# 28Pins_Schematic.net
KiCad netlist of a schematic drawn in Altium Designer
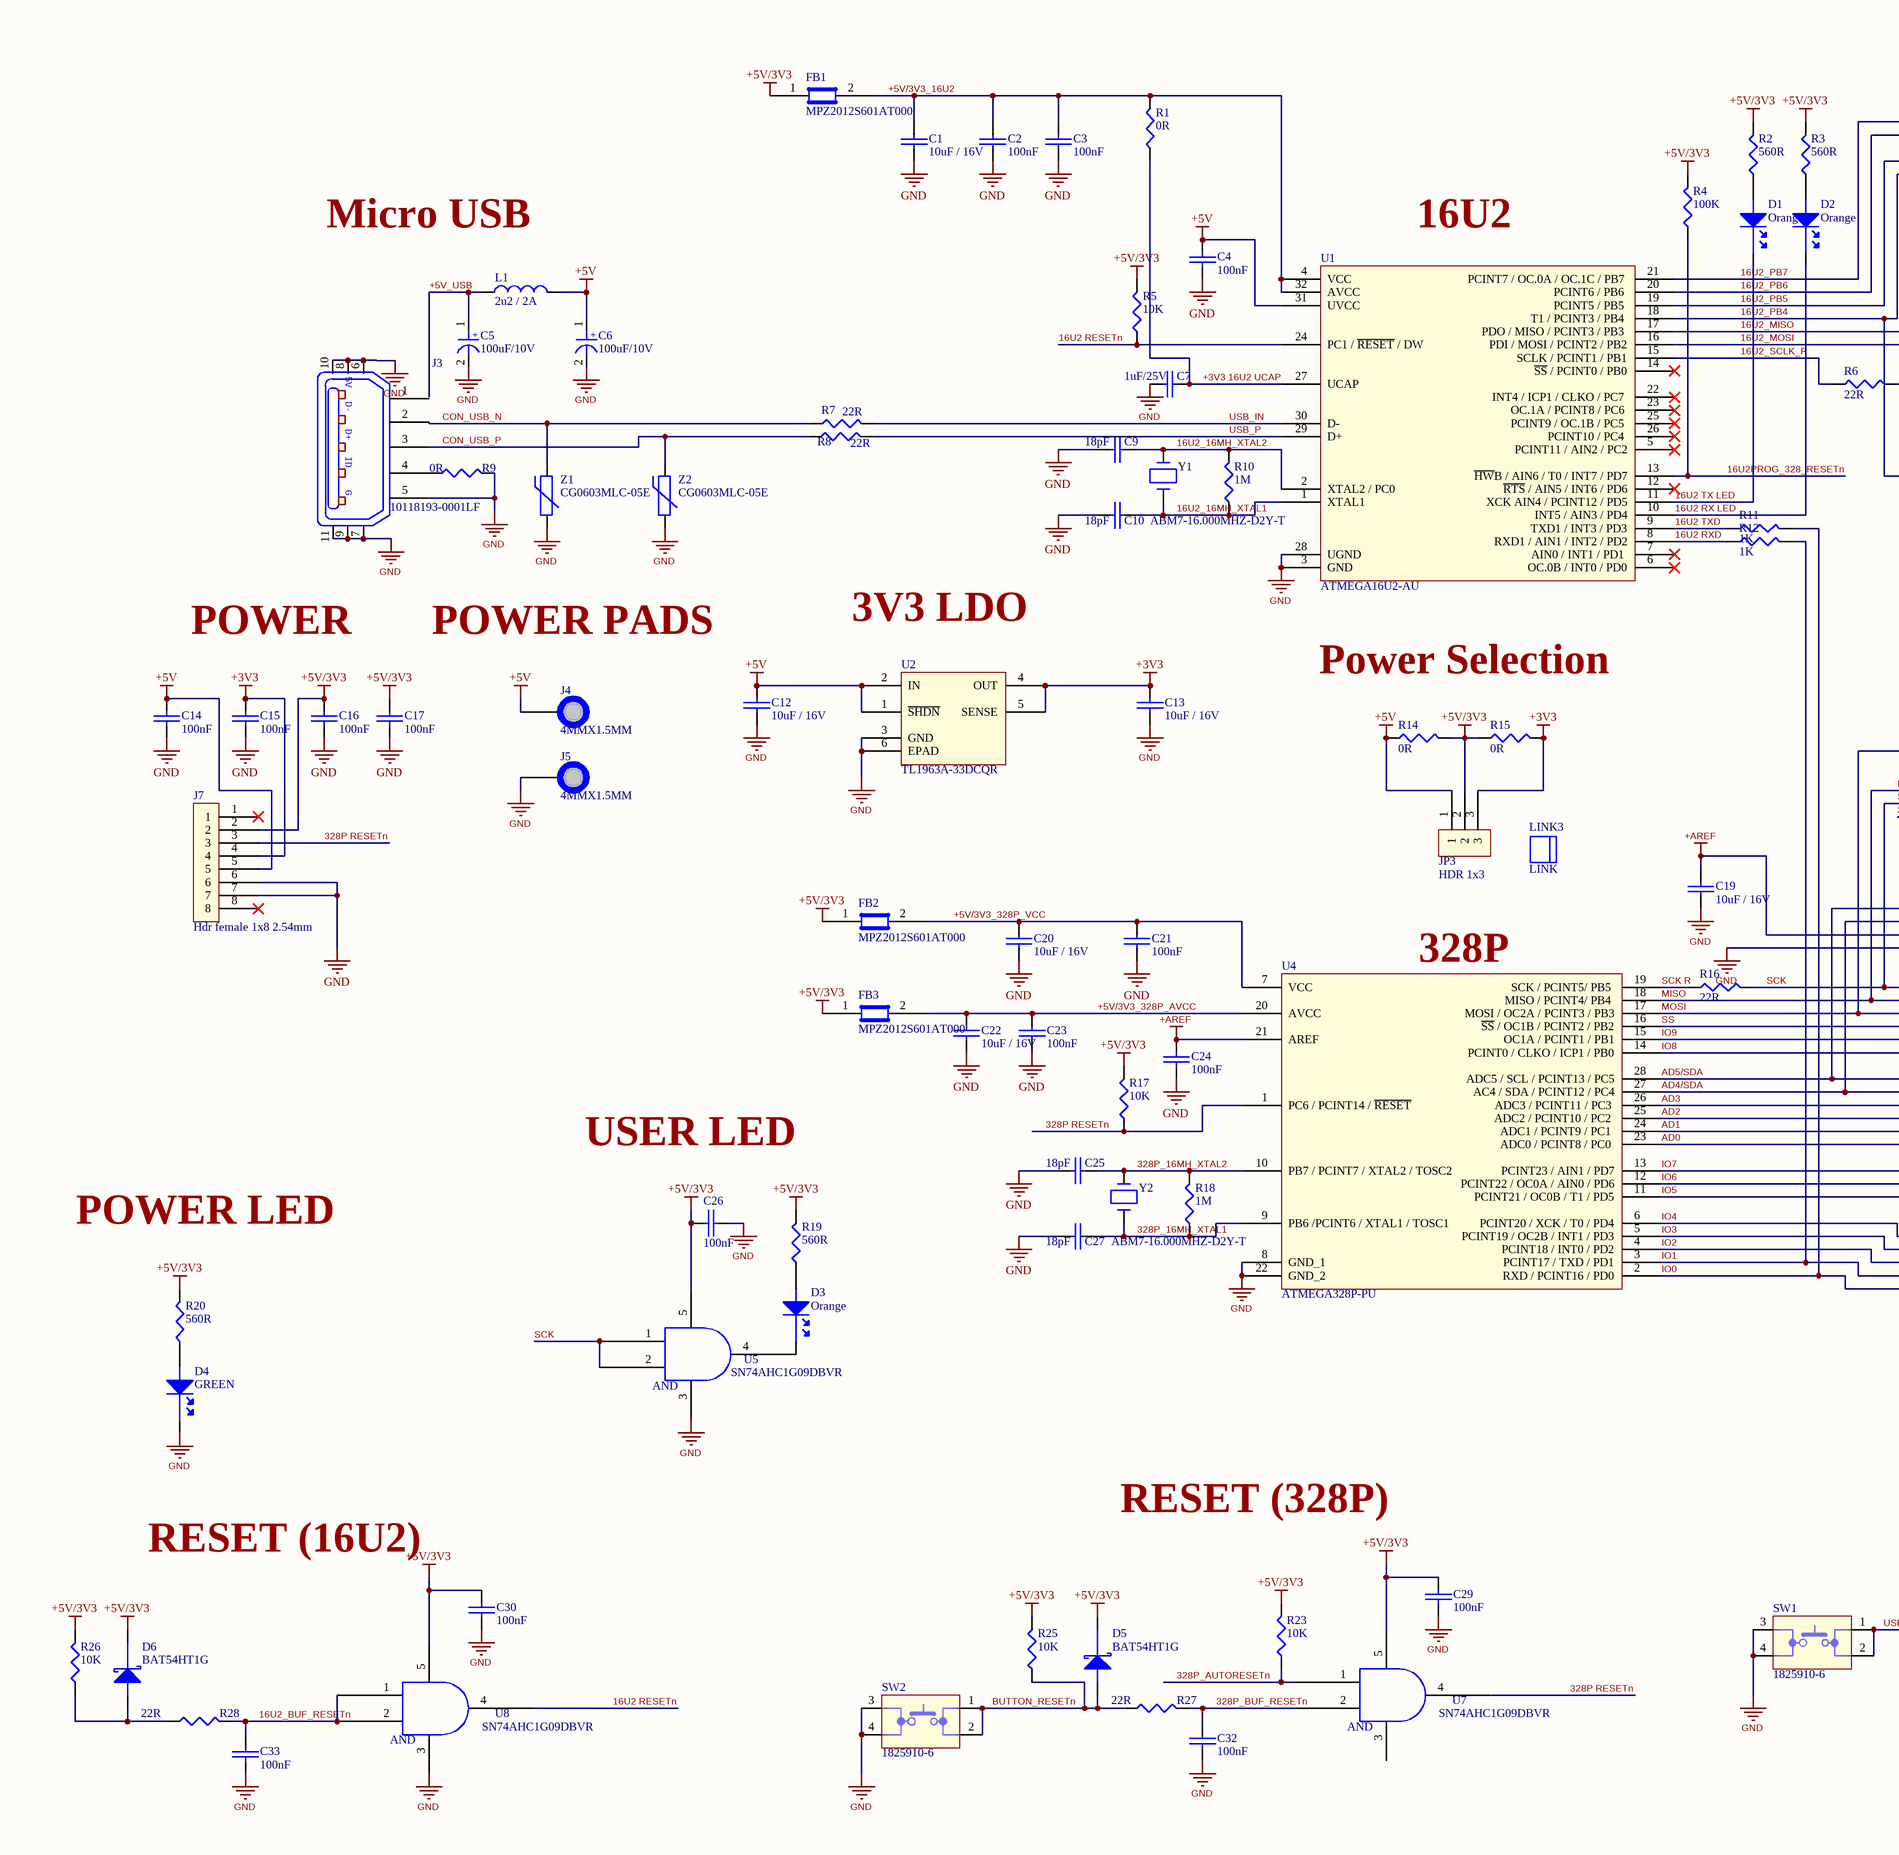
[diagram p0: 28Pins_Schematic.SchDoc, left]
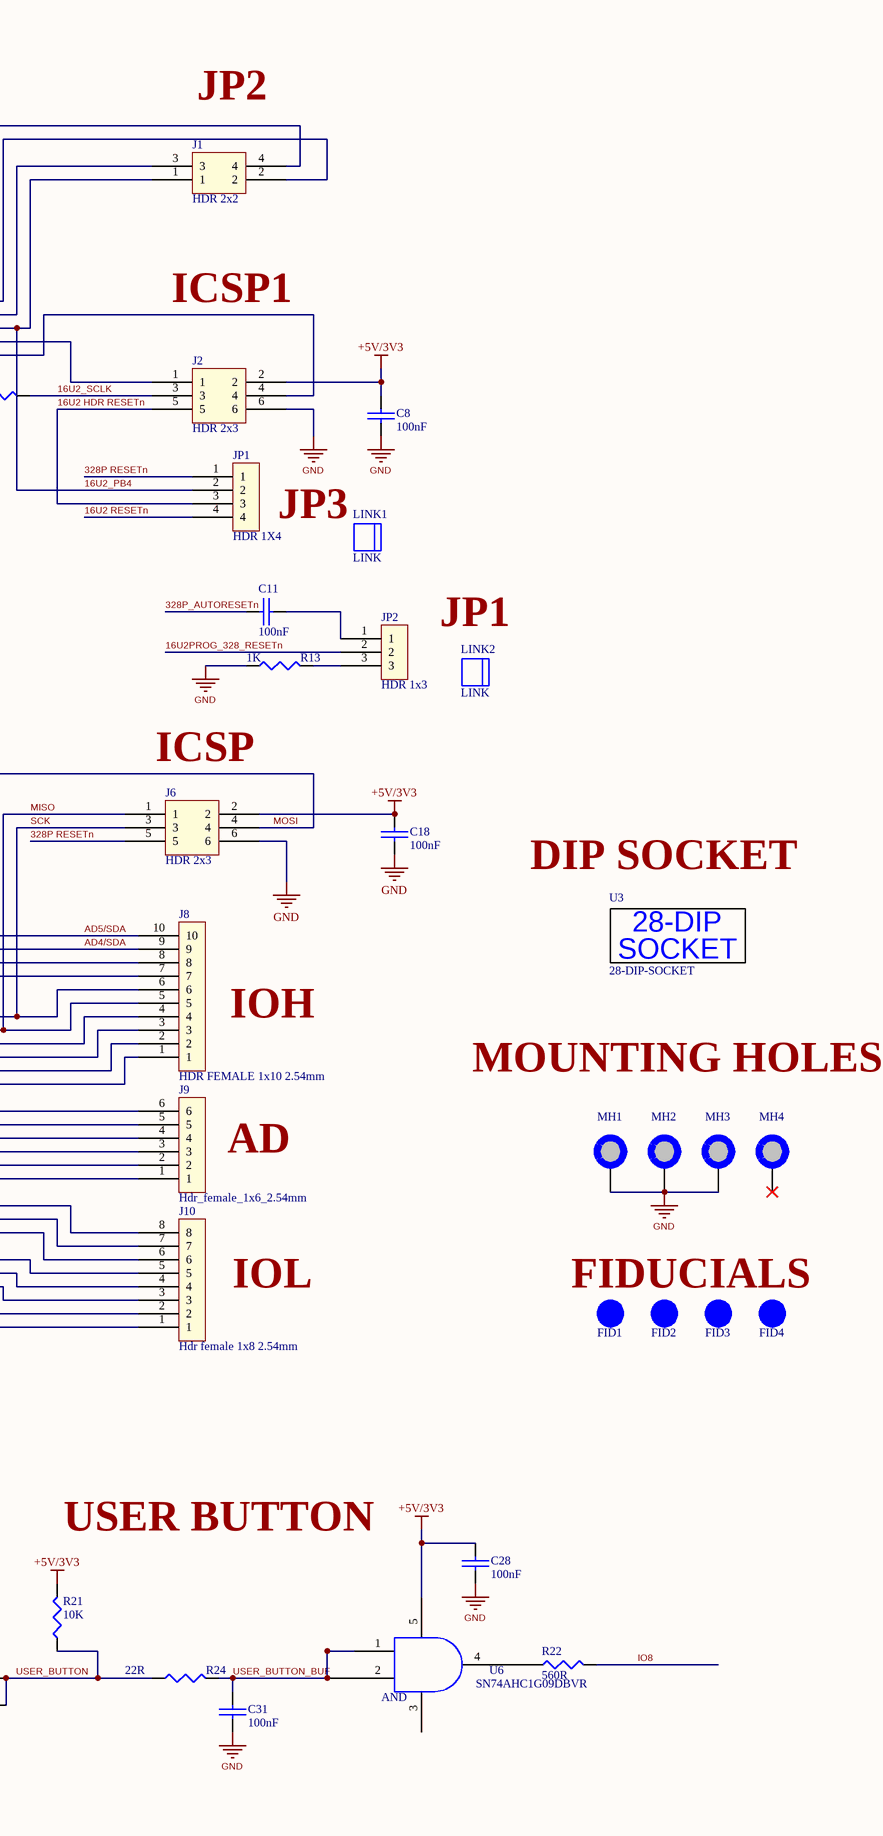
[diagram p1: 28Pins_Schematic.SchDoc, right]

(export (version "E")
  (design (tool "Eeschema 10.0.6"))
  (components
    (comp (ref "C1")
      (value "10uF / 16V")
      (footprint "C0805")
      (fields (field (name "TOLERANCE") "20%"))
      (libsource (lib "28Pins_Project_Schlib") (part "C2012X5R1C106M125AC"))
    )
    (comp (ref "C2")
      (value "100nF")
      (footprint "C0805")
      (fields (field (name "TOLERANCE") "10%") (field (name "VOLTAGE") "50V"))
      (libsource (lib "28Pins_Project_Schlib") (part "C2012X7R1H104K085AA"))
    )
    (comp (ref "C3")
      (value "100nF")
      (footprint "C0805")
      (fields (field (name "TOLERANCE") "10%") (field (name "VOLTAGE") "50V"))
      (libsource (lib "28Pins_Project_Schlib") (part "C2012X7R1H104K085AA"))
    )
    (comp (ref "C4")
      (value "100nF")
      (footprint "C0805")
      (fields (field (name "TOLERANCE") "10%") (field (name "VOLTAGE") "50V"))
      (libsource (lib "28Pins_Project_Schlib") (part "C2012X7R1H104K085AA"))
    )
    (comp (ref "C5")
      (value "100uF/10V")
      (footprint "C_ALU_C_SIZE")
      (description "Cap Aluminum 100uF 10V 20% (5 X 5.4mm) SMD 50mA 1000 hr 85°C T/R")
      (fields (field (name "TOLERANCE") "20%"))
      (libsource (lib "28Pins_Project_Schlib") (part "EEE-1AA101WR"))
    )
    (comp (ref "C6")
      (value "100uF/10V")
      (footprint "C_ALU_C_SIZE")
      (description "Cap Aluminum 100uF 10V 20% (5 X 5.4mm) SMD 50mA 1000 hr 85°C T/R")
      (fields (field (name "TOLERANCE") "20%"))
      (libsource (lib "28Pins_Project_Schlib") (part "EEE-1AA101WR"))
    )
    (comp (ref "C7")
      (value "1uF/25V")
      (footprint "C0805")
      (fields (field (name "TOLERANCE") "10%") (field (name "VOLTAGE") "25V"))
      (libsource (lib "28Pins_Project_Schlib") (part "C2012X5R1E105K125AA"))
    )
    (comp (ref "C8")
      (value "100nF")
      (footprint "C0805")
      (fields (field (name "TOLERANCE") "10%") (field (name "VOLTAGE") "50V"))
      (libsource (lib "28Pins_Project_Schlib") (part "C2012X7R1H104K085AA"))
    )
    (comp (ref "C9")
      (value "18pF")
      (footprint "C0805")
      (description "CAP CER 18PF 50V C0G/NP0 0805")
      (fields (field (name "VOLTAGE") "50V") (field (name "TOLERANCE") "5%"))
      (libsource (lib "28Pins_Project_Schlib") (part "C0805C180J5GACTU"))
    )
    (comp (ref "C10")
      (value "18pF")
      (footprint "C0805")
      (description "CAP CER 18PF 50V C0G/NP0 0805")
      (fields (field (name "VOLTAGE") "50V") (field (name "TOLERANCE") "5%"))
      (libsource (lib "28Pins_Project_Schlib") (part "C0805C180J5GACTU"))
    )
    (comp (ref "C11")
      (value "100nF")
      (footprint "C0805")
      (fields (field (name "TOLERANCE") "10%") (field (name "VOLTAGE") "50V"))
      (libsource (lib "28Pins_Project_Schlib") (part "C2012X7R1H104K085AA"))
    )
    (comp (ref "C12")
      (value "10uF / 16V")
      (footprint "C0805")
      (fields (field (name "TOLERANCE") "20%"))
      (libsource (lib "28Pins_Project_Schlib") (part "C2012X5R1C106M125AC"))
    )
    (comp (ref "C13")
      (value "10uF / 16V")
      (footprint "C0805")
      (fields (field (name "TOLERANCE") "20%"))
      (libsource (lib "28Pins_Project_Schlib") (part "C2012X5R1C106M125AC"))
    )
    (comp (ref "C14")
      (value "100nF")
      (footprint "C0805")
      (fields (field (name "TOLERANCE") "10%") (field (name "VOLTAGE") "50V"))
      (libsource (lib "28Pins_Project_Schlib") (part "C2012X7R1H104K085AA"))
    )
    (comp (ref "C15")
      (value "100nF")
      (footprint "C0805")
      (fields (field (name "TOLERANCE") "10%") (field (name "VOLTAGE") "50V"))
      (libsource (lib "28Pins_Project_Schlib") (part "C2012X7R1H104K085AA"))
    )
    (comp (ref "C16")
      (value "100nF")
      (footprint "C0805")
      (fields (field (name "TOLERANCE") "10%") (field (name "VOLTAGE") "50V"))
      (libsource (lib "28Pins_Project_Schlib") (part "C2012X7R1H104K085AA"))
    )
    (comp (ref "C17")
      (value "100nF")
      (footprint "C0805")
      (fields (field (name "TOLERANCE") "10%") (field (name "VOLTAGE") "50V"))
      (libsource (lib "28Pins_Project_Schlib") (part "C2012X7R1H104K085AA"))
    )
    (comp (ref "C18")
      (value "100nF")
      (footprint "C0805")
      (fields (field (name "TOLERANCE") "10%") (field (name "VOLTAGE") "50V"))
      (libsource (lib "28Pins_Project_Schlib") (part "C2012X7R1H104K085AA"))
    )
    (comp (ref "C19")
      (value "10uF / 16V")
      (footprint "C0805")
      (fields (field (name "TOLERANCE") "20%"))
      (libsource (lib "28Pins_Project_Schlib") (part "C2012X5R1C106M125AC"))
    )
    (comp (ref "C20")
      (value "10uF / 16V")
      (footprint "C0805")
      (fields (field (name "TOLERANCE") "20%"))
      (libsource (lib "28Pins_Project_Schlib") (part "C2012X5R1C106M125AC"))
    )
    (comp (ref "C21")
      (value "100nF")
      (footprint "C0805")
      (fields (field (name "TOLERANCE") "10%") (field (name "VOLTAGE") "50V"))
      (libsource (lib "28Pins_Project_Schlib") (part "C2012X7R1H104K085AA"))
    )
    (comp (ref "C22")
      (value "10uF / 16V")
      (footprint "C0805")
      (fields (field (name "TOLERANCE") "20%"))
      (libsource (lib "28Pins_Project_Schlib") (part "C2012X5R1C106M125AC"))
    )
    (comp (ref "C23")
      (value "100nF")
      (footprint "C0805")
      (fields (field (name "TOLERANCE") "10%") (field (name "VOLTAGE") "50V"))
      (libsource (lib "28Pins_Project_Schlib") (part "C2012X7R1H104K085AA"))
    )
    (comp (ref "C24")
      (value "100nF")
      (footprint "C0805")
      (fields (field (name "TOLERANCE") "10%") (field (name "VOLTAGE") "50V"))
      (libsource (lib "28Pins_Project_Schlib") (part "C2012X7R1H104K085AA"))
    )
    (comp (ref "C25")
      (value "18pF")
      (footprint "C0805")
      (description "CAP CER 18PF 50V C0G/NP0 0805")
      (fields (field (name "VOLTAGE") "50V") (field (name "TOLERANCE") "5%"))
      (libsource (lib "28Pins_Project_Schlib") (part "C0805C180J5GACTU"))
    )
    (comp (ref "C26")
      (value "100nF")
      (footprint "C0805")
      (fields (field (name "TOLERANCE") "10%") (field (name "VOLTAGE") "50V"))
      (libsource (lib "28Pins_Project_Schlib") (part "C2012X7R1H104K085AA"))
    )
    (comp (ref "C27")
      (value "18pF")
      (footprint "C0805")
      (description "CAP CER 18PF 50V C0G/NP0 0805")
      (fields (field (name "VOLTAGE") "50V") (field (name "TOLERANCE") "5%"))
      (libsource (lib "28Pins_Project_Schlib") (part "C0805C180J5GACTU"))
    )
    (comp (ref "C28")
      (value "100nF")
      (footprint "C0805")
      (fields (field (name "TOLERANCE") "10%") (field (name "VOLTAGE") "50V"))
      (libsource (lib "28Pins_Project_Schlib") (part "C2012X7R1H104K085AA"))
    )
    (comp (ref "C29")
      (value "100nF")
      (footprint "C0805")
      (fields (field (name "TOLERANCE") "10%") (field (name "VOLTAGE") "50V"))
      (libsource (lib "28Pins_Project_Schlib") (part "C2012X7R1H104K085AA"))
    )
    (comp (ref "C30")
      (value "100nF")
      (footprint "C0805")
      (fields (field (name "TOLERANCE") "10%") (field (name "VOLTAGE") "50V"))
      (libsource (lib "28Pins_Project_Schlib") (part "C2012X7R1H104K085AA"))
    )
    (comp (ref "C31")
      (value "100nF")
      (footprint "C0805")
      (fields (field (name "TOLERANCE") "10%") (field (name "VOLTAGE") "50V"))
      (libsource (lib "28Pins_Project_Schlib") (part "C2012X7R1H104K085AA"))
    )
    (comp (ref "C32")
      (value "100nF")
      (footprint "C0805")
      (fields (field (name "TOLERANCE") "10%") (field (name "VOLTAGE") "50V"))
      (libsource (lib "28Pins_Project_Schlib") (part "C2012X7R1H104K085AA"))
    )
    (comp (ref "C33")
      (value "100nF")
      (footprint "C0805")
      (fields (field (name "TOLERANCE") "10%") (field (name "VOLTAGE") "50V"))
      (libsource (lib "28Pins_Project_Schlib") (part "C2012X7R1H104K085AA"))
    )
    (comp (ref "D1")
      (value "Orange")
      (footprint "LED_0603")
      (description "OSRAM - LO L29K-H2K1-24-Z - SMARTLED 0603 ORANGE")
      (libsource (lib "28Pins_Project_Schlib") (part "LOL29K-H2K1-24-Z"))
    )
    (comp (ref "D2")
      (value "Orange")
      (footprint "LED_0603")
      (description "OSRAM - LO L29K-H2K1-24-Z - SMARTLED 0603 ORANGE")
      (libsource (lib "28Pins_Project_Schlib") (part "LOL29K-H2K1-24-Z"))
    )
    (comp (ref "D3")
      (value "Orange")
      (footprint "LED_0603")
      (description "OSRAM - LO L29K-H2K1-24-Z - SMARTLED 0603 ORANGE")
      (libsource (lib "28Pins_Project_Schlib") (part "LOL29K-H2K1-24-Z"))
    )
    (comp (ref "D4")
      (value "GREEN")
      (footprint "LED_0603")
      (description "LED Uni-Color Green 572nm 2-Pin Chip 0603(1608Metric) T/R")
      (libsource (lib "28Pins_Project_Schlib") (part "LGL29K-G2J1-24-Z"))
    )
    (comp (ref "D5")
      (value "BAT54HT1G")
      (footprint "SOD323")
      (description "Small Signal Schottky Diode, Single, 30 V, 200 mA, 800 mV, 600 mA, 150 C ;RoHS Compliant: Yes")
      (libsource (lib "28Pins_Project_Schlib") (part "BAT54HT1G"))
    )
    (comp (ref "D6")
      (value "BAT54HT1G")
      (footprint "SOD323")
      (description "Small Signal Schottky Diode, Single, 30 V, 200 mA, 800 mV, 600 mA, 150 C ;RoHS Compliant: Yes")
      (libsource (lib "28Pins_Project_Schlib") (part "BAT54HT1G"))
    )
    (comp (ref "FB1")
      (value "MPZ2012S601AT000")
      (footprint "C0805")
      (description "FERRITE BEAD 600 OHM 0805 1LN")
      (libsource (lib "28Pins_Project_Schlib") (part "MPZ2012S601AT000"))
    )
    (comp (ref "FB2")
      (value "MPZ2012S601AT000")
      (footprint "C0805")
      (description "FERRITE BEAD 600 OHM 0805 1LN")
      (libsource (lib "28Pins_Project_Schlib") (part "MPZ2012S601AT000"))
    )
    (comp (ref "FB3")
      (value "MPZ2012S601AT000")
      (footprint "C0805")
      (description "FERRITE BEAD 600 OHM 0805 1LN")
      (libsource (lib "28Pins_Project_Schlib") (part "MPZ2012S601AT000"))
    )
    (comp (ref "FID1")
      (value "FID_1MMC")
      (footprint "FID_40X120D")
      (description "Fiducial 40mill Diameter,120mil Mask")
      (libsource (lib "28Pins_Project_Schlib") (part "FID_1MM"))
    )
    (comp (ref "FID2")
      (value "FID_1MMC")
      (footprint "FID_40X120D")
      (description "Fiducial 40mill Diameter,120mil Mask")
      (libsource (lib "28Pins_Project_Schlib") (part "FID_1MM"))
    )
    (comp (ref "FID3")
      (value "FID_1MMC")
      (footprint "FID_40X120D")
      (description "Fiducial 40mill Diameter,120mil Mask")
      (libsource (lib "28Pins_Project_Schlib") (part "FID_1MM"))
    )
    (comp (ref "FID4")
      (value "FID_1MMC")
      (footprint "FID_40X120D")
      (description "Fiducial 40mill Diameter,120mil Mask")
      (libsource (lib "28Pins_Project_Schlib") (part "FID_1MM"))
    )
    (comp (ref "J1")
      (value "HDR 2x2")
      (footprint "HDR _2x2_2.54mm")
      (description "CONN HEADER VERT 4POS 2.54MM")
      (libsource (lib "28Pins_Project_Schlib") (part "68602-204HLF"))
    )
    (comp (ref "J2")
      (value "HDR 2x3")
      (footprint "HDR _2x3_2.54mm - duplicate")
      (description "CONN HEADER 6POS .100 STR 30AU")
      (libsource (lib "28Pins_Project_Schlib") (part "67997-106HLF"))
    )
    (comp (ref "J3")
      (value "10118193-0001LF")
      (footprint "10118193")
      (description "CONN USB MICRO B RECPT SMT R/A")
      (libsource (lib "28Pins_Project_Schlib") (part "10118193-0001LF"))
    )
    (comp (ref "J4")
      (value "4MMX1.5MM")
      (footprint "PAD_WITH_HOLE_4MMX1.5MM")
      (description "PAD_WITH_HOLE_4MMX1.5MM")
      (libsource (lib "28Pins_Project_Schlib") (part "PAD_WITH_HOLE_4MMX1.5MM"))
    )
    (comp (ref "J5")
      (value "4MMX1.5MM")
      (footprint "PAD_WITH_HOLE_4MMX1.5MM")
      (description "PAD_WITH_HOLE_4MMX1.5MM")
      (libsource (lib "28Pins_Project_Schlib") (part "PAD_WITH_HOLE_4MMX1.5MM"))
    )
    (comp (ref "J6")
      (value "HDR 2x3")
      (footprint "HDR _2x3_2.54mm - duplicate")
      (description "CONN HEADER 6POS .100 STR 30AU")
      (libsource (lib "28Pins_Project_Schlib") (part "67997-106HLF"))
    )
    (comp (ref "J7")
      (value "Hdr female 1x8 2.54mm")
      (footprint "Hdr_Female_1x8_2.54mm - duplicate")
      (description "2.54mm (0.1\") Pitch SIL Vertical PC Tail Socket Assembly, selective gold + tin, 8 contacts")
      (libsource (lib "28Pins_Project_Schlib") (part "M20-7820842"))
    )
    (comp (ref "J8")
      (value "HDR FEMALE 1x10 2.54mm")
      (footprint "Hdr_Female_1x10_2.54mm - duplicate")
      (description "Headers & Wire Housings 10 PIN SIL VERTICAL SOCKET GOLD+TIN")
      (libsource (lib "28Pins_Project_Schlib") (part "M20-7821042"))
    )
    (comp (ref "J9")
      (value "Hdr_female_1x6_2.54mm")
      (footprint "Hdr_Female_1x6_2.54mm - duplicate - duplicate")
      (description "06-WAY SIL VERT SOCKET L/FREE")
      (libsource (lib "28Pins_Project_Schlib") (part "M20-7820646"))
    )
    (comp (ref "J10")
      (value "Hdr female 1x8 2.54mm")
      (footprint "Hdr_Female_1x8_2.54mm - duplicate")
      (description "2.54mm (0.1\") Pitch SIL Vertical PC Tail Socket Assembly, selective gold + tin, 8 contacts")
      (libsource (lib "") (part "M20-7820842_1"))
    )
    (comp (ref "JP1")
      (value "HDR 1X4")
      (footprint "HDR_1X4_2.54mm")
      (description "CONN HEADER VERT 4POS 2.54MM")
      (libsource (lib "28Pins_Project_Schlib") (part "68001-204HLF"))
    )
    (comp (ref "JP2")
      (value "HDR 1x3")
      (footprint "HDR 1x3 2.54mm")
      (description "Conn Unshrouded Header HDR 3 POS 2.54mm Solder ST Thru-Hole Bulk")
      (libsource (lib "") (part "68000-103HLF_1"))
    )
    (comp (ref "JP3")
      (value "HDR 1x3")
      (footprint "HDR 1x3 2.54mm")
      (description "Conn Unshrouded Header HDR 3 POS 2.54mm Solder ST Thru-Hole Bulk")
      (libsource (lib "28Pins_Project_Schlib") (part "68000-103HLF"))
    )
    (comp (ref "L1")
      (value "2u2 / 2A")
      (footprint "C1210_IND")
      (description "FIXED IND 2.2UH 2A 80 MOHM SMD")
      (fields (field (name "TOLERANCE") "20%"))
      (libsource (lib "28Pins_Project_Schlib") (part "L1210R2R2MDWIT"))
    )
    (comp (ref "LINK1")
      (value "LINK")
      (description "CONN JUMPER SHORTING .100\" GOLD")
      (libsource (lib "28Pins_Project_Schlib") (part "QPC02SXGN-RC"))
    )
    (comp (ref "LINK2")
      (value "LINK")
      (description "CONN JUMPER SHORTING .100\" GOLD")
      (libsource (lib "28Pins_Project_Schlib") (part "QPC02SXGN-RC"))
    )
    (comp (ref "LINK3")
      (value "LINK")
      (description "CONN JUMPER SHORTING .100\" GOLD")
      (libsource (lib "28Pins_Project_Schlib") (part "QPC02SXGN-RC"))
    )
    (comp (ref "MH1")
      (value "MH_7.4MMC_3.2MMD")
      (footprint "MH_7.4MMD_3.2MMD")
      (description "Mounting Hole 7.4mm Diameter, 3.2mm Drill")
      (libsource (lib "28Pins_Project_Schlib") (part "MH_7.4MMC_3.2MMD"))
    )
    (comp (ref "MH2")
      (value "MH_7.4MMC_3.2MMD")
      (footprint "MH_7.4MMD_3.2MMD")
      (description "Mounting Hole 7.4mm Diameter, 3.2mm Drill")
      (libsource (lib "28Pins_Project_Schlib") (part "MH_7.4MMC_3.2MMD"))
    )
    (comp (ref "MH3")
      (value "MH_7.4MMC_3.2MMD")
      (footprint "MH_7.4MMD_3.2MMD")
      (description "Mounting Hole 7.4mm Diameter, 3.2mm Drill")
      (libsource (lib "28Pins_Project_Schlib") (part "MH_7.4MMC_3.2MMD"))
    )
    (comp (ref "MH4")
      (value "MH_7.4MMNC_3.2MMD")
      (footprint "MH_7.4MMD_3.2MMD_NON_COPPER_NPTH")
      (description "Hole 7.4mm Diameter (Non Copper), 3.2mm Drill NPTH")
      (libsource (lib "28Pins_Project_Schlib") (part "MH_7.4MMNC_3.2MMD"))
    )
    (comp (ref "R1")
      (value "0R")
      (footprint "R0805")
      (description "Surface Mount Thick Film Resistor, RC Series, 125 mW, - 5%, 150 V, 0805 [2012 Metric]")
      (fields (field (name "TOLERANCE") "5%"))
      (libsource (lib "28Pins_Project_Schlib") (part "RC0805JR-070RL"))
    )
    (comp (ref "R2")
      (value "560R")
      (footprint "R0805")
      (description "Surface Mount Thick Film Resistor, RC Series, 560 ohm, 125 mW, - 1%, 150 V, 0805 [2012 Metric]")
      (fields (field (name "TOLERANCE") "1%"))
      (libsource (lib "28Pins_Project_Schlib") (part "RC0805FR-07560RL"))
    )
    (comp (ref "R3")
      (value "560R")
      (footprint "R0805")
      (description "Surface Mount Thick Film Resistor, RC Series, 560 ohm, 125 mW, - 1%, 150 V, 0805 [2012 Metric]")
      (fields (field (name "TOLERANCE") "1%"))
      (libsource (lib "28Pins_Project_Schlib") (part "RC0805FR-07560RL"))
    )
    (comp (ref "R4")
      (value "100K")
      (footprint "R0805")
      (description "YAGEO         RC0805FR-07100KL            RES, THICK FILM, 100K, 1%, 0.125W, 0805, REEL")
      (fields (field (name "TOLERANCE") "1%"))
      (libsource (lib "28Pins_Project_Schlib") (part "RC0805FR-07100KL"))
    )
    (comp (ref "R5")
      (value "10K")
      (footprint "R0805")
      (description "RES SMD 10K OHM 1% 1/8W 0805")
      (fields (field (name "TOLERANCE") "1%"))
      (libsource (lib "28Pins_Project_Schlib") (part "RC0805FR-0710KL"))
    )
    (comp (ref "R6")
      (value "22R")
      (footprint "R0805")
      (fields (field (name "TOLERANCE") "1%"))
      (libsource (lib "28Pins_Project_Schlib") (part "RC0805FR-07220RL"))
    )
    (comp (ref "R7")
      (value "22R")
      (footprint "R0805")
      (fields (field (name "TOLERANCE") "1%"))
      (libsource (lib "28Pins_Project_Schlib") (part "RC0805FR-07220RL"))
    )
    (comp (ref "R8")
      (value "22R")
      (footprint "R0805")
      (fields (field (name "TOLERANCE") "1%"))
      (libsource (lib "28Pins_Project_Schlib") (part "RC0805FR-07220RL"))
    )
    (comp (ref "R9")
      (value "0R")
      (footprint "R0805")
      (description "Surface Mount Thick Film Resistor, RC Series, 125 mW, - 5%, 150 V, 0805 [2012 Metric]")
      (fields (field (name "TOLERANCE") "5%"))
      (libsource (lib "28Pins_Project_Schlib") (part "RC0805JR-070RL"))
    )
    (comp (ref "R10")
      (value "1M")
      (footprint "R0805")
      (description "RES SMD 1M OHM 1% 1/8W 0805")
      (fields (field (name "TOLERANCE") "1%"))
      (libsource (lib "28Pins_Project_Schlib") (part "RC0805FR-071ML"))
    )
    (comp (ref "R11")
      (value "1K")
      (footprint "R0805")
      (fields (field (name "TOLERANCE") "1%"))
      (libsource (lib "28Pins_Project_Schlib") (part "RC0805FR-071KL"))
    )
    (comp (ref "R12")
      (value "1K")
      (footprint "R0805")
      (fields (field (name "TOLERANCE") "1%"))
      (libsource (lib "28Pins_Project_Schlib") (part "RC0805FR-071KL"))
    )
    (comp (ref "R13")
      (value "1K")
      (footprint "R0805")
      (fields (field (name "TOLERANCE") "1%"))
      (libsource (lib "28Pins_Project_Schlib") (part "RC0805FR-071KL"))
    )
    (comp (ref "R14")
      (value "0R")
      (footprint "R0805")
      (description "Surface Mount Thick Film Resistor, RC Series, 125 mW, - 5%, 150 V, 0805 [2012 Metric]")
      (fields (field (name "TOLERANCE") "5%"))
      (libsource (lib "28Pins_Project_Schlib") (part "RC0805JR-070RL"))
    )
    (comp (ref "R15")
      (value "0R")
      (footprint "R0805")
      (description "Surface Mount Thick Film Resistor, RC Series, 125 mW, - 5%, 150 V, 0805 [2012 Metric]")
      (fields (field (name "TOLERANCE") "5%"))
      (libsource (lib "28Pins_Project_Schlib") (part "RC0805JR-070RL"))
    )
    (comp (ref "R16")
      (value "22R")
      (footprint "R0805")
      (fields (field (name "TOLERANCE") "1%"))
      (libsource (lib "28Pins_Project_Schlib") (part "RC0805FR-07220RL"))
    )
    (comp (ref "R17")
      (value "10K")
      (footprint "R0805")
      (description "RES SMD 10K OHM 1% 1/8W 0805")
      (fields (field (name "TOLERANCE") "1%"))
      (libsource (lib "28Pins_Project_Schlib") (part "RC0805FR-0710KL"))
    )
    (comp (ref "R18")
      (value "1M")
      (footprint "R0805")
      (description "RES SMD 1M OHM 1% 1/8W 0805")
      (fields (field (name "TOLERANCE") "1%"))
      (libsource (lib "28Pins_Project_Schlib") (part "RC0805FR-071ML"))
    )
    (comp (ref "R19")
      (value "560R")
      (footprint "R0805")
      (description "Surface Mount Thick Film Resistor, RC Series, 560 ohm, 125 mW, - 1%, 150 V, 0805 [2012 Metric]")
      (fields (field (name "TOLERANCE") "1%"))
      (libsource (lib "28Pins_Project_Schlib") (part "RC0805FR-07560RL"))
    )
    (comp (ref "R20")
      (value "560R")
      (footprint "R0805")
      (description "Surface Mount Thick Film Resistor, RC Series, 560 ohm, 125 mW, - 1%, 150 V, 0805 [2012 Metric]")
      (fields (field (name "TOLERANCE") "1%"))
      (libsource (lib "28Pins_Project_Schlib") (part "RC0805FR-07560RL"))
    )
    (comp (ref "R21")
      (value "10K")
      (footprint "R0805")
      (description "RES SMD 10K OHM 1% 1/8W 0805")
      (fields (field (name "TOLERANCE") "1%"))
      (libsource (lib "28Pins_Project_Schlib") (part "RC0805FR-0710KL"))
    )
    (comp (ref "R22")
      (value "560R")
      (footprint "R0805")
      (description "Surface Mount Thick Film Resistor, RC Series, 560 ohm, 125 mW, - 1%, 150 V, 0805 [2012 Metric]")
      (fields (field (name "TOLERANCE") "1%"))
      (libsource (lib "28Pins_Project_Schlib") (part "RC0805FR-07560RL"))
    )
    (comp (ref "R23")
      (value "10K")
      (footprint "R0805")
      (description "RES SMD 10K OHM 1% 1/8W 0805")
      (fields (field (name "TOLERANCE") "1%"))
      (libsource (lib "28Pins_Project_Schlib") (part "RC0805FR-0710KL"))
    )
    (comp (ref "R24")
      (value "22R")
      (footprint "R0805")
      (fields (field (name "TOLERANCE") "1%"))
      (libsource (lib "28Pins_Project_Schlib") (part "RC0805FR-07220RL"))
    )
    (comp (ref "R25")
      (value "10K")
      (footprint "R0805")
      (description "RES SMD 10K OHM 1% 1/8W 0805")
      (fields (field (name "TOLERANCE") "1%"))
      (libsource (lib "28Pins_Project_Schlib") (part "RC0805FR-0710KL"))
    )
    (comp (ref "R26")
      (value "10K")
      (footprint "R0805")
      (description "RES SMD 10K OHM 1% 1/8W 0805")
      (fields (field (name "TOLERANCE") "1%"))
      (libsource (lib "28Pins_Project_Schlib") (part "RC0805FR-0710KL"))
    )
    (comp (ref "R27")
      (value "22R")
      (footprint "R0805")
      (fields (field (name "TOLERANCE") "1%"))
      (libsource (lib "28Pins_Project_Schlib") (part "RC0805FR-07220RL"))
    )
    (comp (ref "R28")
      (value "22R")
      (footprint "R0805")
      (fields (field (name "TOLERANCE") "1%"))
      (libsource (lib "28Pins_Project_Schlib") (part "RC0805FR-07220RL"))
    )
    (comp (ref "SW1")
      (value "1825910-6")
      (footprint "1825910-6")
      (description "SWITCH TACTILE SPST-NO 0.05A 24V")
      (libsource (lib "28Pins_Project_Schlib") (part "1825910-6"))
    )
    (comp (ref "SW2")
      (value "1825910-6")
      (footprint "1825910-6")
      (description "SWITCH TACTILE SPST-NO 0.05A 24V")
      (libsource (lib "28Pins_Project_Schlib") (part "1825910-6"))
    )
    (comp (ref "U1")
      (value "ATMEGA16U2-AU")
      (footprint "TQFP32")
      (description "MICROCHIP - ATMEGA16U2-AU - MCU, 8BIT, MEGAAVR, 16MHZ, TQFP-32")
      (libsource (lib "28Pins_Project_Schlib") (part "ATMEGA16U2-AU"))
    )
    (comp (ref "U2")
      (value "TL1963A-33DCQR")
      (footprint "DCQ (R-PDSO-G6)")
      (description "IC REG LINEAR 3.3V 1.5A SOT223-6")
      (libsource (lib "28Pins_Project_Schlib") (part "TL1963A-33DCQR"))
    )
    (comp (ref "U3")
      (value "28-DIP-SOCKET")
      (footprint "28_DIP_7.62mm_SOCKET")
      (description "CONN IC DIP SOCKET 28POS TIN")
      (libsource (lib "28Pins_Project_Schlib") (part "4828-3004-CP"))
    )
    (comp (ref "U4")
      (value "ATMEGA328P-PU")
      (footprint "28_DIP_7.62m")
      (description "ATMEGA328P-PU; 8 bit Microcontroller AVR 20MHz 1; 32kb Flash; 2kb RAM; I2C SPI 2")
      (libsource (lib "28Pins_Project_Schlib") (part "ATMEGA328P-PU"))
    )
    (comp (ref "U5")
      (value "SN74AHC1G09DBVR")
      (footprint "DBV_SSOT_23_5")
      (description "TEXAS INSTRUMENTS - SN74AHC1G09DBVR - AND Gate, 74AHC1G09, 2 Input, 2 V to 5.5 V, SOT-23-5")
      (libsource (lib "28Pins_Project_Schlib") (part "SN74AHC1G09DBVR"))
    )
    (comp (ref "U6")
      (value "SN74AHC1G09DBVR")
      (footprint "DBV_SSOT_23_5")
      (description "TEXAS INSTRUMENTS - SN74AHC1G09DBVR - AND Gate, 74AHC1G09, 2 Input, 2 V to 5.5 V, SOT-23-5")
      (libsource (lib "28Pins_Project_Schlib") (part "SN74AHC1G09DBVR"))
    )
    (comp (ref "U7")
      (value "SN74AHC1G09DBVR")
      (footprint "DBV_SSOT_23_5")
      (description "TEXAS INSTRUMENTS - SN74AHC1G09DBVR - AND Gate, 74AHC1G09, 2 Input, 2 V to 5.5 V, SOT-23-5")
      (libsource (lib "28Pins_Project_Schlib") (part "SN74AHC1G09DBVR"))
    )
    (comp (ref "U8")
      (value "SN74AHC1G09DBVR")
      (footprint "DBV_SSOT_23_5")
      (description "TEXAS INSTRUMENTS - SN74AHC1G09DBVR - AND Gate, 74AHC1G09, 2 Input, 2 V to 5.5 V, SOT-23-5")
      (libsource (lib "28Pins_Project_Schlib") (part "SN74AHC1G09DBVR"))
    )
    (comp (ref "Y1")
      (value "ABM7-16.000MHZ-D2Y-T")
      (footprint "ABM7_v1_1_BIG")
      (description "CRYSTAL 16.0000MHZ 18PF SMD")
      (fields (field (name "TOLERANCE") "20ppm"))
      (libsource (lib "28Pins_Project_Schlib") (part "ABM7-16.000MHZ-D2Y-T"))
    )
    (comp (ref "Y2")
      (value "ABM7-16.000MHZ-D2Y-T")
      (footprint "ABM7_v1_1_BIG")
      (description "CRYSTAL 16.0000MHZ 18PF SMD")
      (fields (field (name "TOLERANCE") "20ppm"))
      (libsource (lib "28Pins_Project_Schlib") (part "ABM7-16.000MHZ-D2Y-T"))
    )
    (comp (ref "Z1")
      (value "CG0603MLC-05E")
      (footprint "R0603")
      (description "VARISTOR 0603")
      (fields (field (name "VOLTAGE") "5V"))
      (libsource (lib "28Pins_Project_Schlib") (part "CG0603MLC-05E"))
    )
    (comp (ref "Z2")
      (value "CG0603MLC-05E")
      (footprint "R0603")
      (description "VARISTOR 0603")
      (fields (field (name "VOLTAGE") "5V"))
      (libsource (lib "28Pins_Project_Schlib") (part "CG0603MLC-05E"))
    )
  )
  (nets
    (net (code "1") (name "+3V3") (class "Default")
      (node (ref "C13") (pin "2") (pinfunction "2_2") (pintype "passive"))
      (node (ref "C15") (pin "2") (pinfunction "2_2") (pintype "passive"))
      (node (ref "J7") (pin "4") (pinfunction "4_4") (pintype "passive"))
      (node (ref "JP3") (pin "3") (pinfunction "3_3") (pintype "passive"))
      (node (ref "R15") (pin "2") (pinfunction "2_2") (pintype "passive"))
      (node (ref "U2") (pin "4") (pinfunction "OUT_4") (pintype "passive"))
      (node (ref "U2") (pin "5") (pinfunction "SENSE_5") (pintype "passive"))
    )
    (net (code "2") (name "+5V") (class "Default")
      (node (ref "C12") (pin "2") (pinfunction "2_2") (pintype "passive"))
      (node (ref "C14") (pin "2") (pinfunction "2_2") (pintype "passive"))
      (node (ref "C4") (pin "2") (pinfunction "2_2") (pintype "passive"))
      (node (ref "C6") (pin "1") (pinfunction "1_1") (pintype "passive"))
      (node (ref "J4") (pin "1") (pinfunction "1_1") (pintype "passive"))
      (node (ref "J7") (pin "5") (pinfunction "5_5") (pintype "passive"))
      (node (ref "JP3") (pin "1") (pinfunction "1_1") (pintype "passive"))
      (node (ref "L1") (pin "2") (pinfunction "2_2") (pintype "passive"))
      (node (ref "R14") (pin "1") (pinfunction "1_1") (pintype "passive"))
      (node (ref "U1") (pin "31") (pinfunction "UVCC_31") (pintype "passive"))
      (node (ref "U2") (pin "1") (pinfunction "~{SHDN}_1") (pintype "passive"))
      (node (ref "U2") (pin "2") (pinfunction "IN_2") (pintype "passive"))
    )
    (net (code "3") (name "+5V{slash}3V3") (class "Default")
      (node (ref "C16") (pin "2") (pinfunction "2_2") (pintype "passive"))
      (node (ref "C17") (pin "2") (pinfunction "2_2") (pintype "passive"))
      (node (ref "C18") (pin "2") (pinfunction "2_2") (pintype "passive"))
      (node (ref "C26") (pin "1") (pinfunction "1_1") (pintype "passive"))
      (node (ref "C28") (pin "2") (pinfunction "2_2") (pintype "passive"))
      (node (ref "C29") (pin "2") (pinfunction "2_2") (pintype "passive"))
      (node (ref "C30") (pin "2") (pinfunction "2_2") (pintype "passive"))
      (node (ref "C8") (pin "1") (pinfunction "1_1") (pintype "passive"))
      (node (ref "D5") (pin "1") (pinfunction "Cathode_1") (pintype "passive"))
      (node (ref "D6") (pin "1") (pinfunction "Cathode_1") (pintype "passive"))
      (node (ref "FB1") (pin "1") (pinfunction "1_1") (pintype "passive"))
      (node (ref "FB2") (pin "1") (pinfunction "1_1") (pintype "passive"))
      (node (ref "FB3") (pin "1") (pinfunction "1_1") (pintype "passive"))
      (node (ref "J2") (pin "2") (pinfunction "2_2") (pintype "passive"))
      (node (ref "J6") (pin "2") (pinfunction "2_2") (pintype "passive"))
      (node (ref "J7") (pin "2") (pinfunction "2_2") (pintype "passive"))
      (node (ref "JP3") (pin "2") (pinfunction "2_2") (pintype "passive"))
      (node (ref "R14") (pin "2") (pinfunction "2_2") (pintype "passive"))
      (node (ref "R15") (pin "1") (pinfunction "1_1") (pintype "passive"))
      (node (ref "R17") (pin "2") (pinfunction "2_2") (pintype "passive"))
      (node (ref "R19") (pin "2") (pinfunction "2_2") (pintype "passive"))
      (node (ref "R2") (pin "2") (pinfunction "2_2") (pintype "passive"))
      (node (ref "R20") (pin "2") (pinfunction "2_2") (pintype "passive"))
      (node (ref "R21") (pin "2") (pinfunction "2_2") (pintype "passive"))
      (node (ref "R23") (pin "2") (pinfunction "2_2") (pintype "passive"))
      (node (ref "R25") (pin "2") (pinfunction "2_2") (pintype "passive"))
      (node (ref "R26") (pin "2") (pinfunction "2_2") (pintype "passive"))
      (node (ref "R3") (pin "2") (pinfunction "2_2") (pintype "passive"))
      (node (ref "R4") (pin "2") (pinfunction "2_2") (pintype "passive"))
      (node (ref "R5") (pin "2") (pinfunction "2_2") (pintype "passive"))
      (node (ref "U5") (pin "5") (pinfunction "5_5") (pintype "passive"))
      (node (ref "U6") (pin "5") (pinfunction "5_5") (pintype "passive"))
      (node (ref "U7") (pin "5") (pinfunction "5_5") (pintype "passive"))
      (node (ref "U8") (pin "5") (pinfunction "5_5") (pintype "passive"))
    )
    (net (code "4") (name "+AREF") (class "Default")
      (node (ref "C19") (pin "2") (pinfunction "2_2") (pintype "passive"))
      (node (ref "C24") (pin "2") (pinfunction "2_2") (pintype "passive"))
      (node (ref "J8") (pin "8") (pinfunction "8_8") (pintype "passive"))
      (node (ref "U4") (pin "21") (pinfunction "AREF_21") (pintype "passive"))
    )
    (net (code "5") (name "/+3V3 16U2 UCAP") (class "Default")
      (node (ref "C7") (pin "2") (pinfunction "2_2") (pintype "passive"))
      (node (ref "R1") (pin "1") (pinfunction "1_1") (pintype "passive"))
      (node (ref "U1") (pin "27") (pinfunction "UCAP_27") (pintype "passive"))
    )
    (net (code "6") (name "/+5V_USB") (class "Default")
      (node (ref "C5") (pin "1") (pinfunction "1_1") (pintype "passive"))
      (node (ref "L1") (pin "1") (pinfunction "1_1") (pintype "passive"))
    )
    (net (code "7") (name "/+5V{slash}3V3_16U2") (class "Default")
      (node (ref "C1") (pin "2") (pinfunction "2_2") (pintype "passive"))
      (node (ref "C2") (pin "2") (pinfunction "2_2") (pintype "passive"))
      (node (ref "C3") (pin "2") (pinfunction "2_2") (pintype "passive"))
      (node (ref "FB1") (pin "2") (pinfunction "2_2") (pintype "passive"))
      (node (ref "R1") (pin "2") (pinfunction "2_2") (pintype "passive"))
      (node (ref "U1") (pin "32") (pinfunction "AVCC_32") (pintype "passive"))
      (node (ref "U1") (pin "4") (pinfunction "VCC_4") (pintype "passive"))
    )
    (net (code "8") (name "/+5V{slash}3V3_328P_AVCC") (class "Default")
      (node (ref "C22") (pin "2") (pinfunction "2_2") (pintype "passive"))
      (node (ref "C23") (pin "2") (pinfunction "2_2") (pintype "passive"))
      (node (ref "FB3") (pin "2") (pinfunction "2_2") (pintype "passive"))
      (node (ref "U4") (pin "20") (pinfunction "AVCC_20") (pintype "passive"))
    )
    (net (code "9") (name "/+5V{slash}3V3_328P_VCC") (class "Default")
      (node (ref "C20") (pin "2") (pinfunction "2_2") (pintype "passive"))
      (node (ref "C21") (pin "2") (pinfunction "2_2") (pintype "passive"))
      (node (ref "FB2") (pin "2") (pinfunction "2_2") (pintype "passive"))
      (node (ref "U4") (pin "7") (pinfunction "VCC_7") (pintype "passive"))
    )
    (net (code "10") (name "/16U2 HDR RESETn") (class "Default")
      (node (ref "J2") (pin "5") (pinfunction "5_5") (pintype "passive"))
      (node (ref "JP1") (pin "3") (pinfunction "3_3") (pintype "passive"))
    )
    (net (code "11") (name "/16U2 RESETn") (class "Default")
      (node (ref "JP1") (pin "4") (pinfunction "4_4") (pintype "passive"))
      (node (ref "R5") (pin "1") (pinfunction "1_1") (pintype "passive"))
      (node (ref "U1") (pin "24") (pinfunction "PC1_/_~{RESET}_/_DW_24") (pintype "passive"))
      (node (ref "U8") (pin "4") (pinfunction "4_4") (pintype "passive"))
    )
    (net (code "12") (name "/16U2 RX LED") (class "Default")
      (node (ref "D2") (pin "1") (pinfunction "Cathode_1") (pintype "passive"))
      (node (ref "U1") (pin "10") (pinfunction "INT5_/_AIN3_/_PD4_10") (pintype "passive"))
    )
    (net (code "13") (name "/16U2 RXD") (class "Default")
      (node (ref "R12") (pin "1") (pinfunction "1_1") (pintype "passive"))
      (node (ref "U1") (pin "8") (pinfunction "RXD1_/_AIN1_/_INT2_/_PD2_8") (pintype "passive"))
    )
    (net (code "14") (name "/16U2 TX LED") (class "Default")
      (node (ref "D1") (pin "1") (pinfunction "Cathode_1") (pintype "passive"))
      (node (ref "U1") (pin "11") (pinfunction "XCK_AIN4_/_PCINT12_/_PD5_11") (pintype "passive"))
    )
    (net (code "15") (name "/16U2 TXD") (class "Default")
      (node (ref "R11") (pin "1") (pinfunction "1_1") (pintype "passive"))
      (node (ref "U1") (pin "9") (pinfunction "TXD1_/_INT3_/_PD3_9") (pintype "passive"))
    )
    (net (code "16") (name "/16U2PROG_328_RESETn") (class "Default")
      (node (ref "JP2") (pin "2") (pinfunction "2_2") (pintype "passive"))
      (node (ref "R4") (pin "1") (pinfunction "1_1") (pintype "passive"))
      (node (ref "U1") (pin "13") (pinfunction "~{HW}B_/_AIN6_/_T0_/_INT7_/_PD7_13") (pintype "passive"))
    )
    (net (code "17") (name "/16U2_16MH_XTAL1") (class "Default")
      (node (ref "C10") (pin "2") (pinfunction "2_2") (pintype "passive"))
      (node (ref "R10") (pin "1") (pinfunction "1_1") (pintype "passive"))
      (node (ref "U1") (pin "1") (pinfunction "XTAL1_1") (pintype "passive"))
      (node (ref "Y1") (pin "1") (pinfunction "1_1") (pintype "passive"))
    )
    (net (code "18") (name "/16U2_16MH_XTAL2") (class "Default")
      (node (ref "C9") (pin "2") (pinfunction "2_2") (pintype "passive"))
      (node (ref "R10") (pin "2") (pinfunction "2_2") (pintype "passive"))
      (node (ref "U1") (pin "2") (pinfunction "XTAL2_/_PC0_2") (pintype "passive"))
      (node (ref "Y1") (pin "2") (pinfunction "2_2") (pintype "passive"))
    )
    (net (code "19") (name "/16U2_BUF_RESETn") (class "Default")
      (node (ref "C33") (pin "2") (pinfunction "2_2") (pintype "passive"))
      (node (ref "R28") (pin "2") (pinfunction "2_2") (pintype "passive"))
      (node (ref "U8") (pin "1") (pinfunction "1_1") (pintype "passive"))
      (node (ref "U8") (pin "2") (pinfunction "2_2") (pintype "passive"))
    )
    (net (code "20") (name "/16U2_MISO") (class "Default")
      (node (ref "J2") (pin "1") (pinfunction "1_1") (pintype "passive"))
      (node (ref "U1") (pin "17") (pinfunction "PDO_/_MISO_/_PCINT3_/_PB3_17") (pintype "passive"))
    )
    (net (code "21") (name "/16U2_MOSI") (class "Default")
      (node (ref "J2") (pin "4") (pinfunction "4_4") (pintype "passive"))
      (node (ref "U1") (pin "16") (pinfunction "PDI_/_MOSI_/_PCINT2_/_PB2_16") (pintype "passive"))
    )
    (net (code "22") (name "/16U2_PB4") (class "Default")
      (node (ref "J1") (pin "1") (pinfunction "1_1") (pintype "passive"))
      (node (ref "JP1") (pin "2") (pinfunction "2_2") (pintype "passive"))
      (node (ref "U1") (pin "18") (pinfunction "T1_/_PCINT3_/_PB4_18") (pintype "passive"))
    )
    (net (code "23") (name "/16U2_PB5") (class "Default")
      (node (ref "J1") (pin "3") (pinfunction "3_3") (pintype "passive"))
      (node (ref "U1") (pin "19") (pinfunction "PCINT5_/_PB5_19") (pintype "passive"))
    )
    (net (code "24") (name "/16U2_PB6") (class "Default")
      (node (ref "J1") (pin "2") (pinfunction "2_2") (pintype "passive"))
      (node (ref "U1") (pin "20") (pinfunction "PCINT6_/_PB6_20") (pintype "passive"))
    )
    (net (code "25") (name "/16U2_PB7") (class "Default")
      (node (ref "J1") (pin "4") (pinfunction "4_4") (pintype "passive"))
      (node (ref "U1") (pin "21") (pinfunction "PCINT7_/_OC.0A_/_OC.1C_/_PB7_21") (pintype "passive"))
    )
    (net (code "26") (name "/16U2_SCLK") (class "Default")
      (node (ref "J2") (pin "3") (pinfunction "3_3") (pintype "passive"))
      (node (ref "R6") (pin "2") (pinfunction "2_2") (pintype "passive"))
    )
    (net (code "27") (name "/16U2_SCLK_R") (class "Default")
      (node (ref "R6") (pin "1") (pinfunction "1_1") (pintype "passive"))
      (node (ref "U1") (pin "15") (pinfunction "SCLK_/_PCINT1_/_PB1_15") (pintype "passive"))
    )
    (net (code "28") (name "/328P RESETn") (class "Default")
      (node (ref "J6") (pin "5") (pinfunction "5_5") (pintype "passive"))
      (node (ref "J7") (pin "3") (pinfunction "3_3") (pintype "passive"))
      (node (ref "JP1") (pin "1") (pinfunction "1_1") (pintype "passive"))
      (node (ref "R17") (pin "1") (pinfunction "1_1") (pintype "passive"))
      (node (ref "U4") (pin "1") (pinfunction "PC6_/_PCINT14_/_~{RESET}_1") (pintype "passive"))
      (node (ref "U7") (pin "4") (pinfunction "4_4") (pintype "passive"))
    )
    (net (code "29") (name "/328P_16MH_XTAL1") (class "Default")
      (node (ref "C27") (pin "2") (pinfunction "2_2") (pintype "passive"))
      (node (ref "R18") (pin "1") (pinfunction "1_1") (pintype "passive"))
      (node (ref "U4") (pin "9") (pinfunction "PB6_/PCINT6_/_XTAL1_/_TOSC1_9") (pintype "passive"))
      (node (ref "Y2") (pin "1") (pinfunction "1_1") (pintype "passive"))
    )
    (net (code "30") (name "/328P_16MH_XTAL2") (class "Default")
      (node (ref "C25") (pin "2") (pinfunction "2_2") (pintype "passive"))
      (node (ref "R18") (pin "2") (pinfunction "2_2") (pintype "passive"))
      (node (ref "U4") (pin "10") (pinfunction "PB7_/_PCINT7_/_XTAL2_/_TOSC2_10") (pintype "passive"))
      (node (ref "Y2") (pin "2") (pinfunction "2_2") (pintype "passive"))
    )
    (net (code "31") (name "/328P_AUTORESETn") (class "Default")
      (node (ref "C11") (pin "1") (pinfunction "1_1") (pintype "passive"))
      (node (ref "R23") (pin "1") (pinfunction "1_1") (pintype "passive"))
      (node (ref "U7") (pin "1") (pinfunction "1_1") (pintype "passive"))
    )
    (net (code "32") (name "/328P_BUF_RESETn") (class "Default")
      (node (ref "C32") (pin "2") (pinfunction "2_2") (pintype "passive"))
      (node (ref "R27") (pin "2") (pinfunction "2_2") (pintype "passive"))
      (node (ref "U7") (pin "2") (pinfunction "2_2") (pintype "passive"))
    )
    (net (code "33") (name "/AD0") (class "Default")
      (node (ref "J9") (pin "1") (pinfunction "1_1") (pintype "passive"))
      (node (ref "U4") (pin "23") (pinfunction "ADC0_/_PCINT8_/_PC0_23") (pintype "passive"))
    )
    (net (code "34") (name "/AD1") (class "Default")
      (node (ref "J9") (pin "2") (pinfunction "2_2") (pintype "passive"))
      (node (ref "U4") (pin "24") (pinfunction "ADC1_/_PCINT9_/_PC1_24") (pintype "passive"))
    )
    (net (code "35") (name "/AD2") (class "Default")
      (node (ref "J9") (pin "3") (pinfunction "3_3") (pintype "passive"))
      (node (ref "U4") (pin "25") (pinfunction "ADC2_/_PCINT10_/_PC2_25") (pintype "passive"))
    )
    (net (code "36") (name "/AD3") (class "Default")
      (node (ref "J9") (pin "4") (pinfunction "4_4") (pintype "passive"))
      (node (ref "U4") (pin "26") (pinfunction "ADC3_/_PCINT11_/_PC3_26") (pintype "passive"))
    )
    (net (code "37") (name "/AD4{slash}SDA") (class "Default")
      (node (ref "J8") (pin "9") (pinfunction "9_9") (pintype "passive"))
      (node (ref "J9") (pin "5") (pinfunction "5_5") (pintype "passive"))
      (node (ref "U4") (pin "27") (pinfunction "AC4_/_SDA_/_PCINT12_/_PC4_27") (pintype "passive"))
    )
    (net (code "38") (name "/AD5{slash}SDA") (class "Default")
      (node (ref "J8") (pin "10") (pinfunction "10_10") (pintype "passive"))
      (node (ref "J9") (pin "6") (pinfunction "6_6") (pintype "passive"))
      (node (ref "U4") (pin "28") (pinfunction "ADC5_/_SCL_/_PCINT13_/_PC5_28") (pintype "passive"))
    )
    (net (code "39") (name "/BUTTON_RESETn") (class "Default")
      (node (ref "D5") (pin "2") (pinfunction "Anode_2") (pintype "passive"))
      (node (ref "R25") (pin "1") (pinfunction "1_1") (pintype "passive"))
      (node (ref "R27") (pin "1") (pinfunction "1_1") (pintype "passive"))
      (node (ref "SW2") (pin "1") (pinfunction "1_1") (pintype "passive"))
      (node (ref "SW2") (pin "2") (pinfunction "2_2") (pintype "passive"))
    )
    (net (code "40") (name "/CON_USB_N") (class "Default")
      (node (ref "J3") (pin "2") (pinfunction "2_2") (pintype "passive"))
      (node (ref "R7") (pin "1") (pinfunction "1_1") (pintype "passive"))
      (node (ref "Z1") (pin "2") (pinfunction "2_2") (pintype "passive"))
    )
    (net (code "41") (name "/CON_USB_P") (class "Default")
      (node (ref "J3") (pin "3") (pinfunction "3_3") (pintype "passive"))
      (node (ref "R8") (pin "1") (pinfunction "1_1") (pintype "passive"))
      (node (ref "Z2") (pin "2") (pinfunction "2_2") (pintype "passive"))
    )
    (net (code "42") (name "/IO0") (class "Default")
      (node (ref "J10") (pin "1") (pinfunction "1_1") (pintype "passive"))
      (node (ref "R11") (pin "2") (pinfunction "2_2") (pintype "passive"))
      (node (ref "U4") (pin "2") (pinfunction "RXD_/_PCINT16_/_PD0_2") (pintype "passive"))
    )
    (net (code "43") (name "/IO1") (class "Default")
      (node (ref "J10") (pin "2") (pinfunction "2_2") (pintype "passive"))
      (node (ref "R12") (pin "2") (pinfunction "2_2") (pintype "passive"))
      (node (ref "U4") (pin "3") (pinfunction "PCINT17_/_TXD_/_PD1_3") (pintype "passive"))
    )
    (net (code "44") (name "/IO2") (class "Default")
      (node (ref "J10") (pin "3") (pinfunction "3_3") (pintype "passive"))
      (node (ref "U4") (pin "4") (pinfunction "PCINT18_/_INT0_/_PD2_4") (pintype "passive"))
    )
    (net (code "45") (name "/IO3") (class "Default")
      (node (ref "J10") (pin "4") (pinfunction "4_4") (pintype "passive"))
      (node (ref "U4") (pin "5") (pinfunction "PCINT19_/_OC2B_/_INT1_/_PD3_5") (pintype "passive"))
    )
    (net (code "46") (name "/IO4") (class "Default")
      (node (ref "J10") (pin "5") (pinfunction "5_5") (pintype "passive"))
      (node (ref "U4") (pin "6") (pinfunction "PCINT20_/_XCK_/_T0_/_PD4_6") (pintype "passive"))
    )
    (net (code "47") (name "/IO5") (class "Default")
      (node (ref "J10") (pin "6") (pinfunction "6_6") (pintype "passive"))
      (node (ref "U4") (pin "11") (pinfunction "PCINT21_/_OC0B_/_T1_/_PD5_11") (pintype "passive"))
    )
    (net (code "48") (name "/IO6") (class "Default")
      (node (ref "J10") (pin "7") (pinfunction "7_7") (pintype "passive"))
      (node (ref "U4") (pin "12") (pinfunction "PCINT22_/_OC0A_/_AIN0_/_PD6_12") (pintype "passive"))
    )
    (net (code "49") (name "/IO7") (class "Default")
      (node (ref "J10") (pin "8") (pinfunction "8_8") (pintype "passive"))
      (node (ref "U4") (pin "13") (pinfunction "PCINT23_/_AIN1_/_PD7_13") (pintype "passive"))
    )
    (net (code "50") (name "/IO8") (class "Default")
      (node (ref "J8") (pin "1") (pinfunction "1_1") (pintype "passive"))
      (node (ref "R22") (pin "2") (pinfunction "2_2") (pintype "passive"))
      (node (ref "U4") (pin "14") (pinfunction "PCINT0_/_CLKO_/_ICP1_/_PB0_14") (pintype "passive"))
    )
    (net (code "51") (name "/IO9") (class "Default")
      (node (ref "J8") (pin "2") (pinfunction "2_2") (pintype "passive"))
      (node (ref "U4") (pin "15") (pinfunction "OC1A_/_PCINT1_/_PB1_15") (pintype "passive"))
    )
    (net (code "52") (name "/MISO") (class "Default")
      (node (ref "J6") (pin "1") (pinfunction "1_1") (pintype "passive"))
      (node (ref "J8") (pin "5") (pinfunction "5_5") (pintype "passive"))
      (node (ref "U4") (pin "18") (pinfunction "MISO_/_PCINT4/_PB4_18") (pintype "passive"))
    )
    (net (code "53") (name "/MOSI") (class "Default")
      (node (ref "J6") (pin "4") (pinfunction "4_4") (pintype "passive"))
      (node (ref "J8") (pin "4") (pinfunction "4_4") (pintype "passive"))
      (node (ref "U4") (pin "17") (pinfunction "MOSI_/_OC2A_/_PCINT3_/_PB3_17") (pintype "passive"))
    )
    (net (code "54") (name "/SCK") (class "Default")
      (node (ref "J6") (pin "3") (pinfunction "3_3") (pintype "passive"))
      (node (ref "J8") (pin "6") (pinfunction "6_6") (pintype "passive"))
      (node (ref "R16") (pin "2") (pinfunction "2_2") (pintype "passive"))
      (node (ref "U5") (pin "1") (pinfunction "1_1") (pintype "passive"))
      (node (ref "U5") (pin "2") (pinfunction "2_2") (pintype "passive"))
    )
    (net (code "55") (name "/SCK R") (class "Default")
      (node (ref "R16") (pin "1") (pinfunction "1_1") (pintype "passive"))
      (node (ref "U4") (pin "19") (pinfunction "SCK_/_PCINT5/_PB5_19") (pintype "passive"))
    )
    (net (code "56") (name "/SS") (class "Default")
      (node (ref "J8") (pin "3") (pinfunction "3_3") (pintype "passive"))
      (node (ref "U4") (pin "16") (pinfunction "~{SS}_/_OC1B_/_PCINT2_/_PB2_16") (pintype "passive"))
    )
    (net (code "57") (name "/USB_IN") (class "Default")
      (node (ref "R7") (pin "2") (pinfunction "2_2") (pintype "passive"))
      (node (ref "U1") (pin "30") (pinfunction "D-_30") (pintype "passive"))
    )
    (net (code "58") (name "/USB_P") (class "Default")
      (node (ref "R8") (pin "2") (pinfunction "2_2") (pintype "passive"))
      (node (ref "U1") (pin "29") (pinfunction "D+_29") (pintype "passive"))
    )
    (net (code "59") (name "/USER_BUTTON") (class "Default")
      (node (ref "R21") (pin "1") (pinfunction "1_1") (pintype "passive"))
      (node (ref "R24") (pin "1") (pinfunction "1_1") (pintype "passive"))
      (node (ref "SW1") (pin "1") (pinfunction "1_1") (pintype "passive"))
      (node (ref "SW1") (pin "2") (pinfunction "2_2") (pintype "passive"))
    )
    (net (code "60") (name "/USER_BUTTON_BUF") (class "Default")
      (node (ref "C31") (pin "2") (pinfunction "2_2") (pintype "passive"))
      (node (ref "R24") (pin "2") (pinfunction "2_2") (pintype "passive"))
      (node (ref "U6") (pin "1") (pinfunction "1_1") (pintype "passive"))
      (node (ref "U6") (pin "2") (pinfunction "2_2") (pintype "passive"))
    )
    (net (code "61") (name "GND") (class "Default")
      (node (ref "C1") (pin "1") (pinfunction "1_1") (pintype "passive"))
      (node (ref "C10") (pin "1") (pinfunction "1_1") (pintype "passive"))
      (node (ref "C12") (pin "1") (pinfunction "1_1") (pintype "passive"))
      (node (ref "C13") (pin "1") (pinfunction "1_1") (pintype "passive"))
      (node (ref "C14") (pin "1") (pinfunction "1_1") (pintype "passive"))
      (node (ref "C15") (pin "1") (pinfunction "1_1") (pintype "passive"))
      (node (ref "C16") (pin "1") (pinfunction "1_1") (pintype "passive"))
      (node (ref "C17") (pin "1") (pinfunction "1_1") (pintype "passive"))
      (node (ref "C18") (pin "1") (pinfunction "1_1") (pintype "passive"))
      (node (ref "C19") (pin "1") (pinfunction "1_1") (pintype "passive"))
      (node (ref "C2") (pin "1") (pinfunction "1_1") (pintype "passive"))
      (node (ref "C20") (pin "1") (pinfunction "1_1") (pintype "passive"))
      (node (ref "C21") (pin "1") (pinfunction "1_1") (pintype "passive"))
      (node (ref "C22") (pin "1") (pinfunction "1_1") (pintype "passive"))
      (node (ref "C23") (pin "1") (pinfunction "1_1") (pintype "passive"))
      (node (ref "C24") (pin "1") (pinfunction "1_1") (pintype "passive"))
      (node (ref "C25") (pin "1") (pinfunction "1_1") (pintype "passive"))
      (node (ref "C26") (pin "2") (pinfunction "2_2") (pintype "passive"))
      (node (ref "C27") (pin "1") (pinfunction "1_1") (pintype "passive"))
      (node (ref "C28") (pin "1") (pinfunction "1_1") (pintype "passive"))
      (node (ref "C29") (pin "1") (pinfunction "1_1") (pintype "passive"))
      (node (ref "C3") (pin "1") (pinfunction "1_1") (pintype "passive"))
      (node (ref "C30") (pin "1") (pinfunction "1_1") (pintype "passive"))
      (node (ref "C31") (pin "1") (pinfunction "1_1") (pintype "passive"))
      (node (ref "C32") (pin "1") (pinfunction "1_1") (pintype "passive"))
      (node (ref "C33") (pin "1") (pinfunction "1_1") (pintype "passive"))
      (node (ref "C4") (pin "1") (pinfunction "1_1") (pintype "passive"))
      (node (ref "C5") (pin "2") (pinfunction "2_2") (pintype "passive"))
      (node (ref "C6") (pin "2") (pinfunction "2_2") (pintype "passive"))
      (node (ref "C7") (pin "1") (pinfunction "1_1") (pintype "passive"))
      (node (ref "C8") (pin "2") (pinfunction "2_2") (pintype "passive"))
      (node (ref "C9") (pin "1") (pinfunction "1_1") (pintype "passive"))
      (node (ref "D4") (pin "1") (pinfunction "Cathode_1") (pintype "passive"))
      (node (ref "J2") (pin "6") (pinfunction "6_6") (pintype "passive"))
      (node (ref "J3") (pin "10") (pinfunction "10_10") (pintype "passive"))
      (node (ref "J3") (pin "11") (pinfunction "11_11") (pintype "passive"))
      (node (ref "J3") (pin "5") (pinfunction "y_5") (pintype "passive"))
      (node (ref "J3") (pin "6") (pinfunction "6_6") (pintype "passive"))
      (node (ref "J3") (pin "7") (pinfunction "7_7") (pintype "passive"))
      (node (ref "J3") (pin "8") (pinfunction "8_8") (pintype "passive"))
      (node (ref "J3") (pin "9") (pinfunction "9_9") (pintype "passive"))
      (node (ref "J5") (pin "1") (pinfunction "1_1") (pintype "passive"))
      (node (ref "J6") (pin "6") (pinfunction "6_6") (pintype "passive"))
      (node (ref "J7") (pin "6") (pinfunction "6_6") (pintype "passive"))
      (node (ref "J7") (pin "7") (pinfunction "7_7") (pintype "passive"))
      (node (ref "J8") (pin "7") (pinfunction "7_7") (pintype "passive"))
      (node (ref "MH1") (pin "1") (pinfunction "1_1") (pintype "passive"))
      (node (ref "MH2") (pin "1") (pinfunction "1_1") (pintype "passive"))
      (node (ref "MH3") (pin "1") (pinfunction "1_1") (pintype "passive"))
      (node (ref "R13") (pin "1") (pinfunction "1_1") (pintype "passive"))
      (node (ref "R9") (pin "2") (pinfunction "2_2") (pintype "passive"))
      (node (ref "SW1") (pin "3") (pinfunction "3_3") (pintype "passive"))
      (node (ref "SW1") (pin "4") (pinfunction "4_4") (pintype "passive"))
      (node (ref "SW2") (pin "3") (pinfunction "3_3") (pintype "passive"))
      (node (ref "SW2") (pin "4") (pinfunction "4_4") (pintype "passive"))
      (node (ref "U1") (pin "28") (pinfunction "UGND_28") (pintype "passive"))
      (node (ref "U1") (pin "3") (pinfunction "GND_3") (pintype "passive"))
      (node (ref "U2") (pin "3") (pinfunction "GND_3") (pintype "passive"))
      (node (ref "U2") (pin "6") (pinfunction "EPAD_6") (pintype "passive"))
      (node (ref "U4") (pin "22") (pinfunction "GND_2_22") (pintype "passive"))
      (node (ref "U4") (pin "8") (pinfunction "GND_1_8") (pintype "passive"))
      (node (ref "U5") (pin "3") (pinfunction "3_3") (pintype "passive"))
      (node (ref "U8") (pin "3") (pinfunction "3_3") (pintype "passive"))
      (node (ref "Z1") (pin "1") (pinfunction "1_1") (pintype "passive"))
      (node (ref "Z2") (pin "1") (pinfunction "1_1") (pintype "passive"))
    )
    (net (code "62") (name "Net-(C11-Pad2)") (class "Default")
      (node (ref "C11") (pin "2") (pinfunction "2_2") (pintype "passive"))
      (node (ref "JP2") (pin "1") (pinfunction "1_1") (pintype "passive"))
    )
    (net (code "63") (name "Net-(D1-Anode)") (class "Default")
      (node (ref "D1") (pin "2") (pinfunction "Anode_2") (pintype "passive"))
      (node (ref "R2") (pin "1") (pinfunction "1_1") (pintype "passive"))
    )
    (net (code "64") (name "Net-(D2-Anode)") (class "Default")
      (node (ref "D2") (pin "2") (pinfunction "Anode_2") (pintype "passive"))
      (node (ref "R3") (pin "1") (pinfunction "1_1") (pintype "passive"))
    )
    (net (code "65") (name "Net-(D3-Anode)") (class "Default")
      (node (ref "D3") (pin "2") (pinfunction "Anode_2") (pintype "passive"))
      (node (ref "R19") (pin "1") (pinfunction "1_1") (pintype "passive"))
    )
    (net (code "66") (name "Net-(D3-Cathode)") (class "Default")
      (node (ref "D3") (pin "1") (pinfunction "Cathode_1") (pintype "passive"))
      (node (ref "U5") (pin "4") (pinfunction "4_4") (pintype "passive"))
    )
    (net (code "67") (name "Net-(D4-Anode)") (class "Default")
      (node (ref "D4") (pin "2") (pinfunction "Anode_2") (pintype "passive"))
      (node (ref "R20") (pin "1") (pinfunction "1_1") (pintype "passive"))
    )
    (net (code "68") (name "Net-(D6-Anode)") (class "Default")
      (node (ref "D6") (pin "2") (pinfunction "Anode_2") (pintype "passive"))
      (node (ref "R26") (pin "1") (pinfunction "1_1") (pintype "passive"))
      (node (ref "R28") (pin "1") (pinfunction "1_1") (pintype "passive"))
    )
    (net (code "69") (name "Net-(J3-Pad4)") (class "Default")
      (node (ref "J3") (pin "4") (pinfunction "4_4") (pintype "passive"))
      (node (ref "R9") (pin "1") (pinfunction "1_1") (pintype "passive"))
    )
    (net (code "70") (name "Net-(JP2-Pad3)") (class "Default")
      (node (ref "JP2") (pin "3") (pinfunction "3_3") (pintype "passive"))
      (node (ref "R13") (pin "2") (pinfunction "2_2") (pintype "passive"))
    )
    (net (code "71") (name "Net-(R22-Pad1)") (class "Default")
      (node (ref "R22") (pin "1") (pinfunction "1_1") (pintype "passive"))
      (node (ref "U6") (pin "4") (pinfunction "4_4") (pintype "passive"))
    )
    (net (code "72") (name "unconnected-(J3-Pad1)") (class "Default")
      (node (ref "J3") (pin "1") (pinfunction "1_1") (pintype "passive"))
    )
    (net (code "73") (name "unconnected-(J7-Pad1)") (class "Default")
      (node (ref "J7") (pin "1") (pinfunction "1_1") (pintype "passive+no_connect"))
    )
    (net (code "74") (name "unconnected-(J7-Pad8)") (class "Default")
      (node (ref "J7") (pin "8") (pinfunction "8_8") (pintype "passive+no_connect"))
    )
    (net (code "75") (name "unconnected-(MH4-Pad1)") (class "Default")
      (node (ref "MH4") (pin "1") (pinfunction "1_1") (pintype "passive+no_connect"))
    )
    (net (code "76") (name "unconnected-(U1-AIN0_{slash}_INT1_{slash}_PD1-Pad7)") (class "Default")
      (node (ref "U1") (pin "7") (pinfunction "AIN0_/_INT1_/_PD1_7") (pintype "passive+no_connect"))
    )
    (net (code "77") (name "unconnected-(U1-INT4_{slash}_ICP1_{slash}_CLKO_{slash}_PC7-Pad22)") (class "Default")
      (node (ref "U1") (pin "22") (pinfunction "INT4_/_ICP1_/_CLKO_/_PC7_22") (pintype "passive+no_connect"))
    )
    (net (code "78") (name "unconnected-(U1-OC.0B_{slash}_INT0_{slash}_PD0-Pad6)") (class "Default")
      (node (ref "U1") (pin "6") (pinfunction "OC.0B_/_INT0_/_PD0_6") (pintype "passive+no_connect"))
    )
    (net (code "79") (name "unconnected-(U1-OC.1A_{slash}_PCINT8_{slash}_PC6-Pad23)") (class "Default")
      (node (ref "U1") (pin "23") (pinfunction "OC.1A_/_PCINT8_/_PC6_23") (pintype "passive+no_connect"))
    )
    (net (code "80") (name "unconnected-(U1-PCINT9_{slash}_OC.1B_{slash}_PC5-Pad25)") (class "Default")
      (node (ref "U1") (pin "25") (pinfunction "PCINT9_/_OC.1B_/_PC5_25") (pintype "passive+no_connect"))
    )
    (net (code "81") (name "unconnected-(U1-PCINT10_{slash}_PC4-Pad26)") (class "Default")
      (node (ref "U1") (pin "26") (pinfunction "PCINT10_/_PC4_26") (pintype "passive+no_connect"))
    )
    (net (code "82") (name "unconnected-(U1-PCINT11_{slash}_AIN2_{slash}_PC2-Pad5)") (class "Default")
      (node (ref "U1") (pin "5") (pinfunction "PCINT11_/_AIN2_/_PC2_5") (pintype "passive+no_connect"))
    )
    (net (code "83") (name "unconnected-(U1-~{RTS}_{slash}_AIN5_{slash}_INT6_{slash}_PD6-Pad12)") (class "Default")
      (node (ref "U1") (pin "12") (pinfunction "~{RTS}_/_AIN5_/_INT6_/_PD6_12") (pintype "passive+no_connect"))
    )
    (net (code "84") (name "unconnected-(U1-~{SS}_{slash}_PCINT0_{slash}_PB0-Pad14)") (class "Default")
      (node (ref "U1") (pin "14") (pinfunction "~{SS}_/_PCINT0_/_PB0_14") (pintype "passive+no_connect"))
    )
    (net (code "85") (name "unconnected-(U6-Pad3)") (class "Default")
      (node (ref "U6") (pin "3") (pinfunction "3_3") (pintype "passive"))
    )
    (net (code "86") (name "unconnected-(U7-Pad3)") (class "Default")
      (node (ref "U7") (pin "3") (pinfunction "3_3") (pintype "passive"))
    )
  )
)
